# untitled.net
KiCad netlist of a schematic drawn in EAGLE
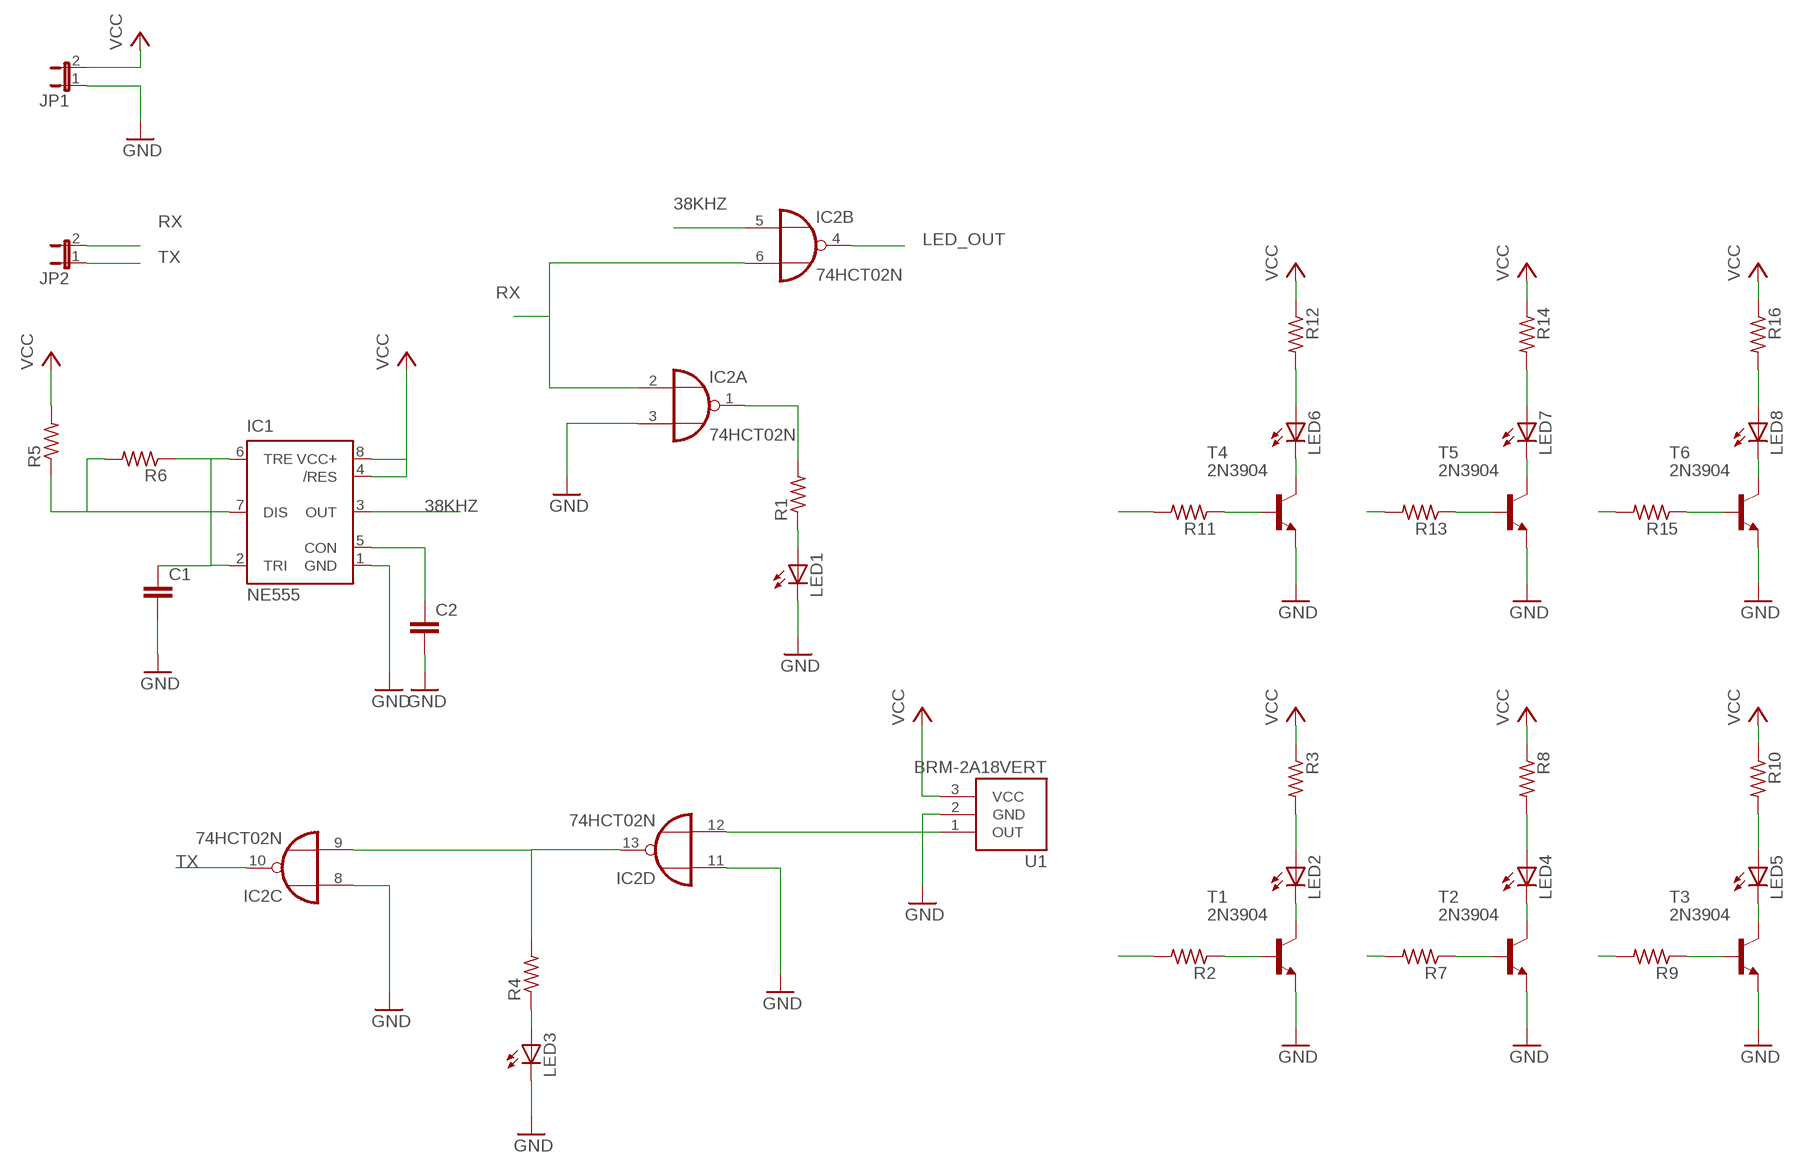
[diagram p0: schematic, sheet 1]

(export (version "E")
  (design (tool "Eeschema 10.0.6"))
  (components
    (comp (ref "C1")
      (value "CAPKIT")
      (footprint "eagle-import:CAP-PTH-SMALL-KIT")
      (libsource (lib "eagle-import") (part "CAPKIT"))
    )
    (comp (ref "C2")
      (value "CAPKIT")
      (footprint "eagle-import:CAP-PTH-SMALL-KIT")
      (libsource (lib "eagle-import") (part "CAPKIT"))
    )
    (comp (ref "IC1")
      (value "NE555")
      (footprint "eagle-import:DIL-08")
      (fields (field (name "MF") "Arrow Electronics") (field (name "MPN") "NE555N"))
      (libsource (lib "eagle-import") (part "NE555"))
    )
    (comp (ref "IC2")
      (value "74HCT02N")
      (footprint "eagle-import:DIL14")
      (libsource (lib "eagle-import") (part "7402NHCT"))
    )
    (comp (ref "JP1")
      (value "JP1E")
      (footprint "eagle-import:JP1")
      (libsource (lib "eagle-import") (part "JP1E"))
    )
    (comp (ref "JP2")
      (value "JP1E")
      (footprint "eagle-import:JP1")
      (libsource (lib "eagle-import") (part "JP1E"))
    )
    (comp (ref "LED1")
      (value "LED5MM")
      (footprint "eagle-import:LED5MM")
      (libsource (lib "eagle-import") (part "LED5MM"))
    )
    (comp (ref "LED2")
      (value "LED5MM")
      (footprint "eagle-import:LED5MM")
      (libsource (lib "eagle-import") (part "LED5MM"))
    )
    (comp (ref "LED3")
      (value "LED5MM")
      (footprint "eagle-import:LED5MM")
      (libsource (lib "eagle-import") (part "LED5MM"))
    )
    (comp (ref "LED4")
      (value "LED5MM")
      (footprint "eagle-import:LED5MM")
      (libsource (lib "eagle-import") (part "LED5MM"))
    )
    (comp (ref "LED5")
      (value "LED5MM")
      (footprint "eagle-import:LED5MM")
      (libsource (lib "eagle-import") (part "LED5MM"))
    )
    (comp (ref "LED6")
      (value "LED5MM")
      (footprint "eagle-import:LED5MM")
      (libsource (lib "eagle-import") (part "LED5MM"))
    )
    (comp (ref "LED7")
      (value "LED5MM")
      (footprint "eagle-import:LED5MM")
      (libsource (lib "eagle-import") (part "LED5MM"))
    )
    (comp (ref "LED8")
      (value "LED5MM")
      (footprint "eagle-import:LED5MM")
      (libsource (lib "eagle-import") (part "LED5MM"))
    )
    (comp (ref "R1")
      (value "R-US_0207/10")
      (footprint "eagle-import:0207_10")
      (libsource (lib "eagle-import") (part "R-US_0207/10"))
    )
    (comp (ref "R2")
      (value "R-US_0207/10")
      (footprint "eagle-import:0207_10")
      (libsource (lib "eagle-import") (part "R-US_0207/10"))
    )
    (comp (ref "R3")
      (value "R-US_0207/10")
      (footprint "eagle-import:0207_10")
      (libsource (lib "eagle-import") (part "R-US_0207/10"))
    )
    (comp (ref "R4")
      (value "R-US_0207/10")
      (footprint "eagle-import:0207_10")
      (libsource (lib "eagle-import") (part "R-US_0207/10"))
    )
    (comp (ref "R5")
      (value "R-US_0207/10")
      (footprint "eagle-import:0207_10")
      (libsource (lib "eagle-import") (part "R-US_0207/10"))
    )
    (comp (ref "R6")
      (value "R-US_0207/10")
      (footprint "eagle-import:0207_10")
      (libsource (lib "eagle-import") (part "R-US_0207/10"))
    )
    (comp (ref "R7")
      (value "R-US_0207/10")
      (footprint "eagle-import:0207_10")
      (libsource (lib "eagle-import") (part "R-US_0207/10"))
    )
    (comp (ref "R8")
      (value "R-US_0207/10")
      (footprint "eagle-import:0207_10")
      (libsource (lib "eagle-import") (part "R-US_0207/10"))
    )
    (comp (ref "R9")
      (value "R-US_0207/10")
      (footprint "eagle-import:0207_10")
      (libsource (lib "eagle-import") (part "R-US_0207/10"))
    )
    (comp (ref "R10")
      (value "R-US_0207/10")
      (footprint "eagle-import:0207_10")
      (libsource (lib "eagle-import") (part "R-US_0207/10"))
    )
    (comp (ref "R11")
      (value "R-US_0207/10")
      (footprint "eagle-import:0207_10")
      (libsource (lib "eagle-import") (part "R-US_0207/10"))
    )
    (comp (ref "R12")
      (value "R-US_0207/10")
      (footprint "eagle-import:0207_10")
      (libsource (lib "eagle-import") (part "R-US_0207/10"))
    )
    (comp (ref "R13")
      (value "R-US_0207/10")
      (footprint "eagle-import:0207_10")
      (libsource (lib "eagle-import") (part "R-US_0207/10"))
    )
    (comp (ref "R14")
      (value "R-US_0207/10")
      (footprint "eagle-import:0207_10")
      (libsource (lib "eagle-import") (part "R-US_0207/10"))
    )
    (comp (ref "R15")
      (value "R-US_0207/10")
      (footprint "eagle-import:0207_10")
      (libsource (lib "eagle-import") (part "R-US_0207/10"))
    )
    (comp (ref "R16")
      (value "R-US_0207/10")
      (footprint "eagle-import:0207_10")
      (libsource (lib "eagle-import") (part "R-US_0207/10"))
    )
    (comp (ref "T1")
      (value "2N3904")
      (footprint "eagle-import:TO92")
      (libsource (lib "eagle-import") (part "2N3904"))
    )
    (comp (ref "T2")
      (value "2N3904")
      (footprint "eagle-import:TO92")
      (libsource (lib "eagle-import") (part "2N3904"))
    )
    (comp (ref "T3")
      (value "2N3904")
      (footprint "eagle-import:TO92")
      (libsource (lib "eagle-import") (part "2N3904"))
    )
    (comp (ref "T4")
      (value "2N3904")
      (footprint "eagle-import:TO92")
      (libsource (lib "eagle-import") (part "2N3904"))
    )
    (comp (ref "T5")
      (value "2N3904")
      (footprint "eagle-import:TO92")
      (libsource (lib "eagle-import") (part "2N3904"))
    )
    (comp (ref "T6")
      (value "2N3904")
      (footprint "eagle-import:TO92")
      (libsource (lib "eagle-import") (part "2N3904"))
    )
    (comp (ref "U1")
      (value "BRM-2A18VERT")
      (footprint "eagle-import:BRM-2508_VERT")
      (libsource (lib "eagle-import") (part "BRM-2A18VERT"))
    )
  )
  (nets
    (net (code "1") (name "/38KHZ") (class "Default")
      (node (ref "IC1") (pin "3") (pinfunction "OUT_3") (pintype "output"))
      (node (ref "IC2") (pin "5") (pinfunction "I0_5") (pintype "input"))
    )
    (net (code "2") (name "/LED_OUT") (class "Default")
      (node (ref "IC2") (pin "4") (pinfunction "O_4") (pintype "output"))
      (node (ref "R11") (pin "2") (pinfunction "2_2") (pintype "passive"))
      (node (ref "R13") (pin "2") (pinfunction "2_2") (pintype "passive"))
      (node (ref "R15") (pin "2") (pinfunction "2_2") (pintype "passive"))
      (node (ref "R2") (pin "2") (pinfunction "2_2") (pintype "passive"))
      (node (ref "R7") (pin "2") (pinfunction "2_2") (pintype "passive"))
      (node (ref "R9") (pin "2") (pinfunction "2_2") (pintype "passive"))
    )
    (net (code "3") (name "/RX") (class "Default")
      (node (ref "IC2") (pin "2") (pinfunction "I0_2") (pintype "input"))
      (node (ref "IC2") (pin "6") (pinfunction "I1_6") (pintype "input"))
      (node (ref "JP2") (pin "2") (pinfunction "2_2") (pintype "passive"))
    )
    (net (code "4") (name "/TX") (class "Default")
      (node (ref "IC2") (pin "10") (pinfunction "O_10") (pintype "output"))
      (node (ref "JP2") (pin "1") (pinfunction "1_1") (pintype "passive"))
    )
    (net (code "5") (name "GND") (class "Default")
      (node (ref "C1") (pin "2") (pinfunction "2_2") (pintype "passive"))
      (node (ref "C2") (pin "2") (pinfunction "2_2") (pintype "passive"))
      (node (ref "IC1") (pin "1") (pinfunction "GND_1") (pintype "power_in"))
      (node (ref "IC2") (pin "11") (pinfunction "I0_11") (pintype "input"))
      (node (ref "IC2") (pin "3") (pinfunction "I1_3") (pintype "input"))
      (node (ref "IC2") (pin "8") (pinfunction "I0_8") (pintype "input"))
      (node (ref "JP1") (pin "1") (pinfunction "1_1") (pintype "passive"))
      (node (ref "LED1") (pin "K") (pinfunction "C_K") (pintype "passive"))
      (node (ref "LED3") (pin "K") (pinfunction "C_K") (pintype "passive"))
      (node (ref "T1") (pin "3") (pinfunction "E_3") (pintype "passive"))
      (node (ref "T2") (pin "3") (pinfunction "E_3") (pintype "passive"))
      (node (ref "T3") (pin "3") (pinfunction "E_3") (pintype "passive"))
      (node (ref "T4") (pin "3") (pinfunction "E_3") (pintype "passive"))
      (node (ref "T5") (pin "3") (pinfunction "E_3") (pintype "passive"))
      (node (ref "T6") (pin "3") (pinfunction "E_3") (pintype "passive"))
      (node (ref "U1") (pin "2") (pinfunction "GND_2") (pintype "bidirectional"))
    )
    (net (code "6") (name "Net-(IC1-CON)") (class "Default")
      (node (ref "C2") (pin "1") (pinfunction "1_1") (pintype "passive"))
      (node (ref "IC1") (pin "5") (pinfunction "CON_5") (pintype "input"))
    )
    (net (code "7") (name "Net-(IC1-DIS)") (class "Default")
      (node (ref "IC1") (pin "7") (pinfunction "DIS_7") (pintype "input"))
      (node (ref "R5") (pin "1") (pinfunction "1_1") (pintype "passive"))
      (node (ref "R6") (pin "2") (pinfunction "2_2") (pintype "passive"))
    )
    (net (code "8") (name "Net-(IC1-TRE)") (class "Default")
      (node (ref "C1") (pin "1") (pinfunction "1_1") (pintype "passive"))
      (node (ref "IC1") (pin "2") (pinfunction "TRI_2") (pintype "input"))
      (node (ref "IC1") (pin "6") (pinfunction "TRE_6") (pintype "input"))
      (node (ref "R6") (pin "1") (pinfunction "1_1") (pintype "passive"))
    )
    (net (code "9") (name "Net-(IC2A-O)") (class "Default")
      (node (ref "IC2") (pin "1") (pinfunction "O_1") (pintype "output"))
      (node (ref "R1") (pin "2") (pinfunction "2_2") (pintype "passive"))
    )
    (net (code "10") (name "Net-(IC2C-I1)") (class "Default")
      (node (ref "IC2") (pin "13") (pinfunction "O_13") (pintype "output"))
      (node (ref "IC2") (pin "9") (pinfunction "I1_9") (pintype "input"))
      (node (ref "R4") (pin "2") (pinfunction "2_2") (pintype "passive"))
    )
    (net (code "11") (name "Net-(IC2D-I1)") (class "Default")
      (node (ref "IC2") (pin "12") (pinfunction "I1_12") (pintype "input"))
      (node (ref "U1") (pin "1") (pinfunction "OUT_1") (pintype "bidirectional"))
    )
    (net (code "12") (name "Net-(LED1-PadA)") (class "Default")
      (node (ref "LED1") (pin "A") (pinfunction "A_A") (pintype "passive"))
      (node (ref "R1") (pin "1") (pinfunction "1_1") (pintype "passive"))
    )
    (net (code "13") (name "Net-(LED2-C)") (class "Default")
      (node (ref "LED2") (pin "K") (pinfunction "C_K") (pintype "passive"))
      (node (ref "T1") (pin "1") (pinfunction "C_1") (pintype "passive"))
    )
    (net (code "14") (name "Net-(LED2-PadA)") (class "Default")
      (node (ref "LED2") (pin "A") (pinfunction "A_A") (pintype "passive"))
      (node (ref "R3") (pin "2") (pinfunction "2_2") (pintype "passive"))
    )
    (net (code "15") (name "Net-(LED3-PadA)") (class "Default")
      (node (ref "LED3") (pin "A") (pinfunction "A_A") (pintype "passive"))
      (node (ref "R4") (pin "1") (pinfunction "1_1") (pintype "passive"))
    )
    (net (code "16") (name "Net-(LED4-C)") (class "Default")
      (node (ref "LED4") (pin "K") (pinfunction "C_K") (pintype "passive"))
      (node (ref "T2") (pin "1") (pinfunction "C_1") (pintype "passive"))
    )
    (net (code "17") (name "Net-(LED4-PadA)") (class "Default")
      (node (ref "LED4") (pin "A") (pinfunction "A_A") (pintype "passive"))
      (node (ref "R8") (pin "2") (pinfunction "2_2") (pintype "passive"))
    )
    (net (code "18") (name "Net-(LED5-C)") (class "Default")
      (node (ref "LED5") (pin "K") (pinfunction "C_K") (pintype "passive"))
      (node (ref "T3") (pin "1") (pinfunction "C_1") (pintype "passive"))
    )
    (net (code "19") (name "Net-(LED5-PadA)") (class "Default")
      (node (ref "LED5") (pin "A") (pinfunction "A_A") (pintype "passive"))
      (node (ref "R10") (pin "2") (pinfunction "2_2") (pintype "passive"))
    )
    (net (code "20") (name "Net-(LED6-C)") (class "Default")
      (node (ref "LED6") (pin "K") (pinfunction "C_K") (pintype "passive"))
      (node (ref "T4") (pin "1") (pinfunction "C_1") (pintype "passive"))
    )
    (net (code "21") (name "Net-(LED6-PadA)") (class "Default")
      (node (ref "LED6") (pin "A") (pinfunction "A_A") (pintype "passive"))
      (node (ref "R12") (pin "2") (pinfunction "2_2") (pintype "passive"))
    )
    (net (code "22") (name "Net-(LED7-C)") (class "Default")
      (node (ref "LED7") (pin "K") (pinfunction "C_K") (pintype "passive"))
      (node (ref "T5") (pin "1") (pinfunction "C_1") (pintype "passive"))
    )
    (net (code "23") (name "Net-(LED7-PadA)") (class "Default")
      (node (ref "LED7") (pin "A") (pinfunction "A_A") (pintype "passive"))
      (node (ref "R14") (pin "2") (pinfunction "2_2") (pintype "passive"))
    )
    (net (code "24") (name "Net-(LED8-C)") (class "Default")
      (node (ref "LED8") (pin "K") (pinfunction "C_K") (pintype "passive"))
      (node (ref "T6") (pin "1") (pinfunction "C_1") (pintype "passive"))
    )
    (net (code "25") (name "Net-(LED8-PadA)") (class "Default")
      (node (ref "LED8") (pin "A") (pinfunction "A_A") (pintype "passive"))
      (node (ref "R16") (pin "2") (pinfunction "2_2") (pintype "passive"))
    )
    (net (code "26") (name "Net-(T1-B)") (class "Default")
      (node (ref "R2") (pin "1") (pinfunction "1_1") (pintype "passive"))
      (node (ref "T1") (pin "2") (pinfunction "B_2") (pintype "passive"))
    )
    (net (code "27") (name "Net-(T2-B)") (class "Default")
      (node (ref "R7") (pin "1") (pinfunction "1_1") (pintype "passive"))
      (node (ref "T2") (pin "2") (pinfunction "B_2") (pintype "passive"))
    )
    (net (code "28") (name "Net-(T3-B)") (class "Default")
      (node (ref "R9") (pin "1") (pinfunction "1_1") (pintype "passive"))
      (node (ref "T3") (pin "2") (pinfunction "B_2") (pintype "passive"))
    )
    (net (code "29") (name "Net-(T4-B)") (class "Default")
      (node (ref "R11") (pin "1") (pinfunction "1_1") (pintype "passive"))
      (node (ref "T4") (pin "2") (pinfunction "B_2") (pintype "passive"))
    )
    (net (code "30") (name "Net-(T5-B)") (class "Default")
      (node (ref "R13") (pin "1") (pinfunction "1_1") (pintype "passive"))
      (node (ref "T5") (pin "2") (pinfunction "B_2") (pintype "passive"))
    )
    (net (code "31") (name "Net-(T6-B)") (class "Default")
      (node (ref "R15") (pin "1") (pinfunction "1_1") (pintype "passive"))
      (node (ref "T6") (pin "2") (pinfunction "B_2") (pintype "passive"))
    )
    (net (code "32") (name "VCC") (class "Default")
      (node (ref "IC1") (pin "4") (pinfunction "/RES_4") (pintype "input"))
      (node (ref "IC1") (pin "8") (pinfunction "VCC+_8") (pintype "power_in"))
      (node (ref "JP1") (pin "2") (pinfunction "2_2") (pintype "passive"))
      (node (ref "R10") (pin "1") (pinfunction "1_1") (pintype "passive"))
      (node (ref "R12") (pin "1") (pinfunction "1_1") (pintype "passive"))
      (node (ref "R14") (pin "1") (pinfunction "1_1") (pintype "passive"))
      (node (ref "R16") (pin "1") (pinfunction "1_1") (pintype "passive"))
      (node (ref "R3") (pin "1") (pinfunction "1_1") (pintype "passive"))
      (node (ref "R5") (pin "2") (pinfunction "2_2") (pintype "passive"))
      (node (ref "R8") (pin "1") (pinfunction "1_1") (pintype "passive"))
      (node (ref "U1") (pin "3") (pinfunction "VCC_3") (pintype "bidirectional"))
    )
  )
)
